# triversity.net
KiCad netlist of a schematic drawn in EAGLE
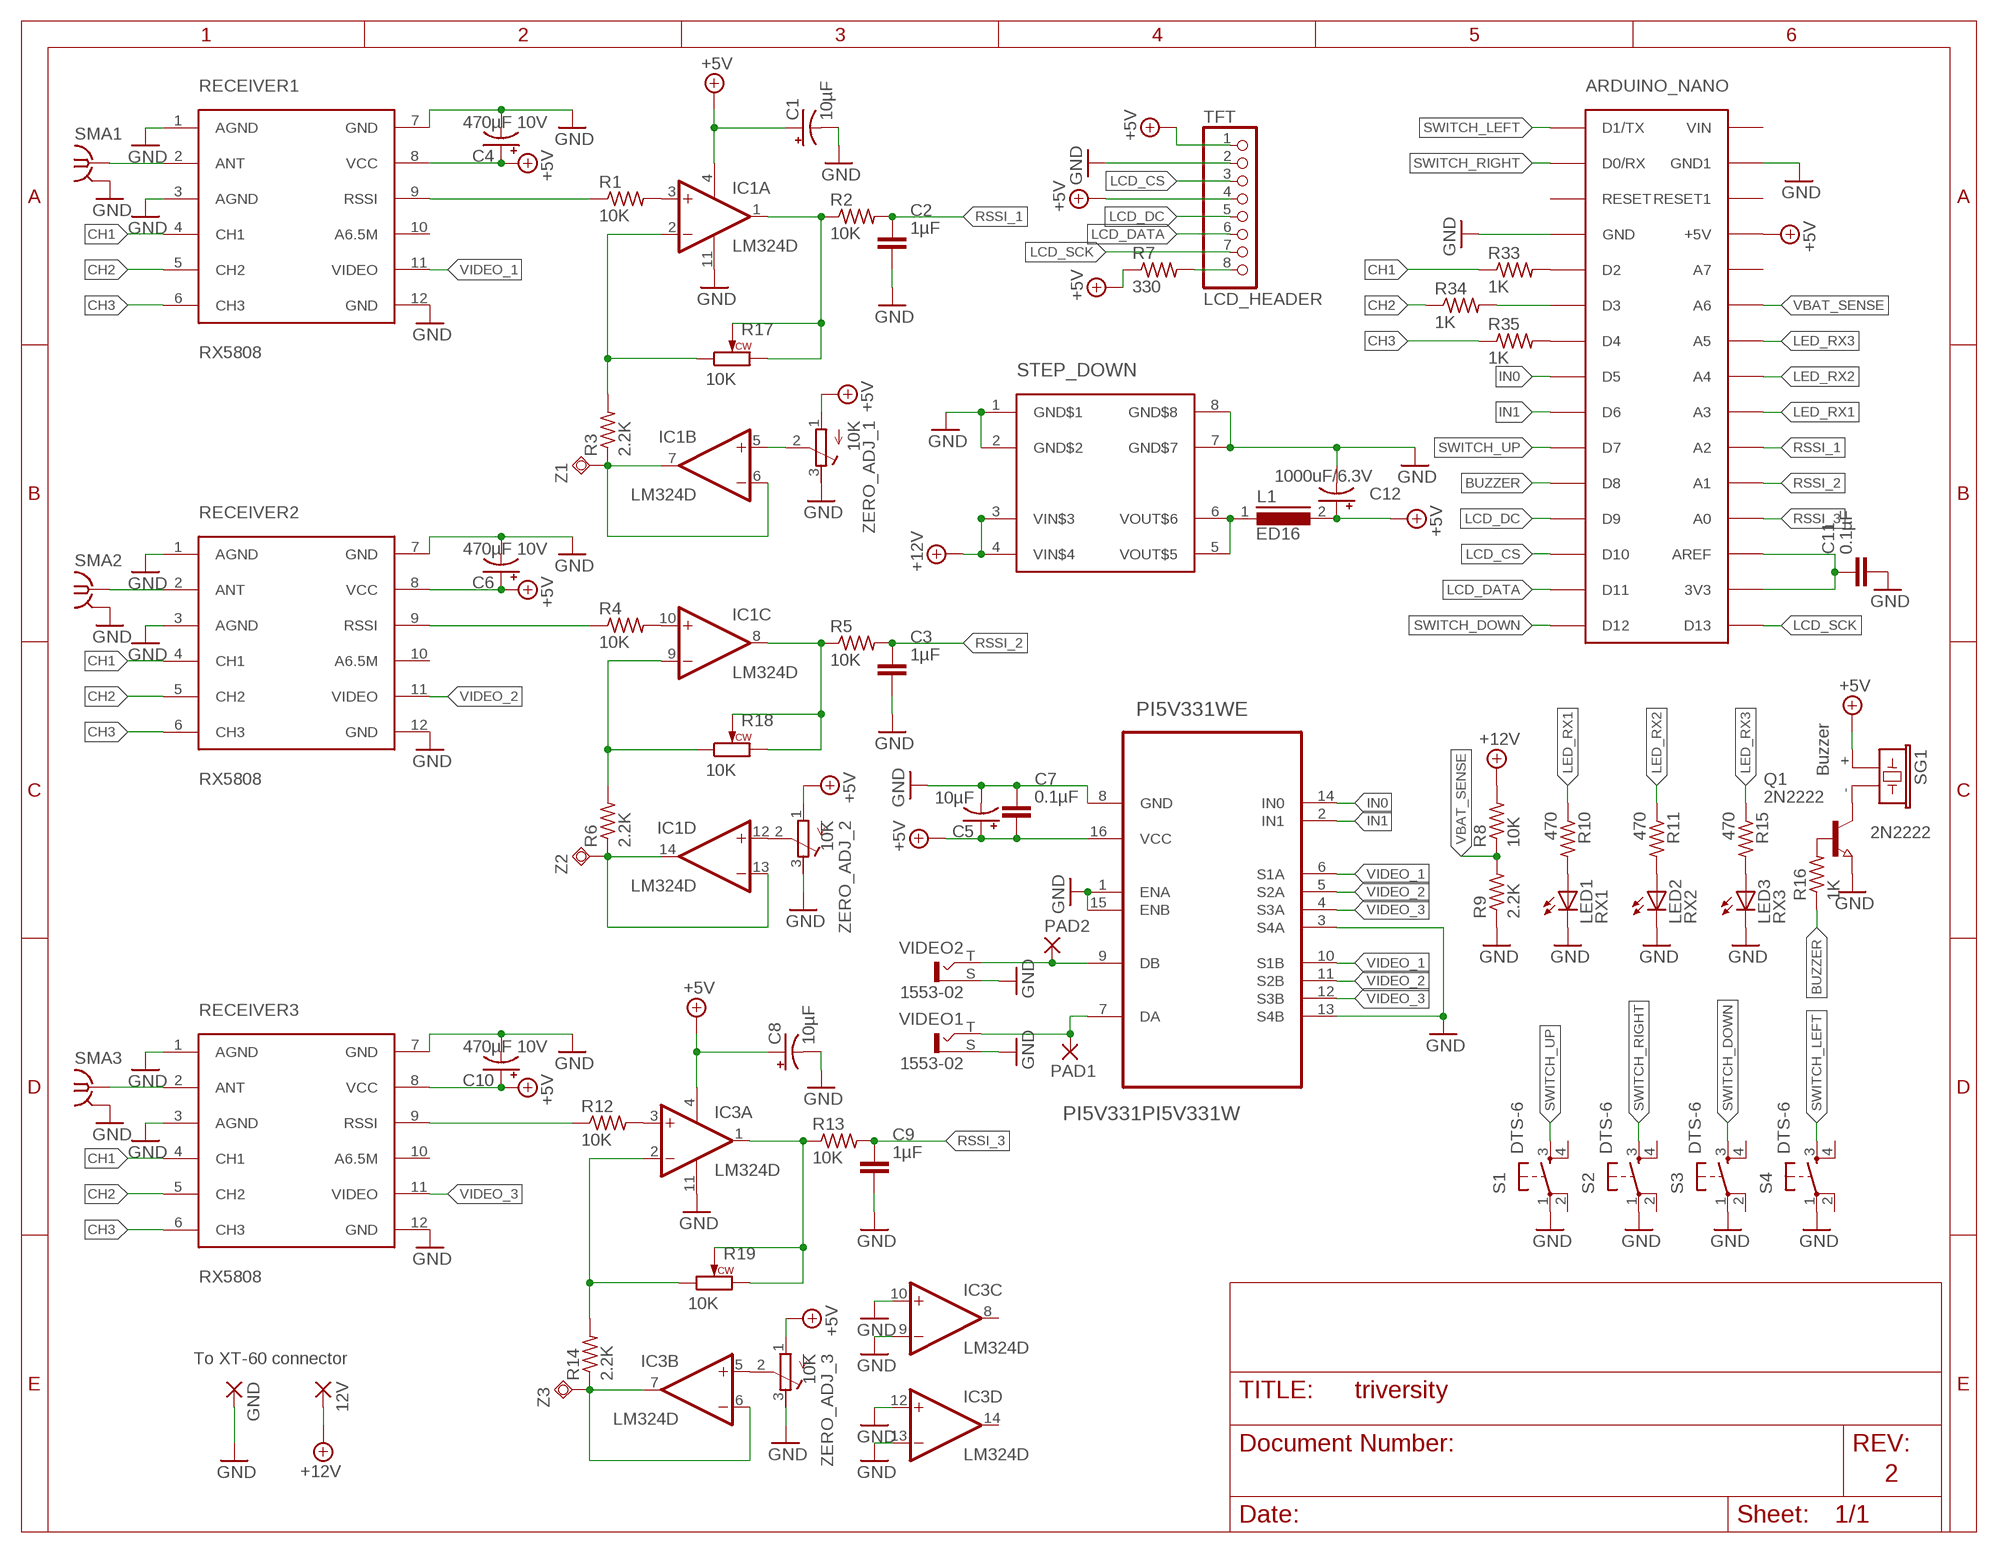
[diagram p0: schematic, sheet 1]

(export (version "E")
  (design (tool "Eeschema 10.0.6"))
  (components
    (comp (ref "12V")
      (value "WIREPAD4,16O1,6")
      (footprint "eagle-import:4,16O1,6")
      (libsource (lib "eagle-import") (part "WIREPAD4,16O1,6"))
    )
    (comp (ref "ARDUINO_NANO")
      (value "ARDUINO_NANO")
      (footprint "eagle-import:PDIP-32")
      (fields (field (name "NAME") "Arduino Nano"))
      (libsource (lib "eagle-import") (part "ARDUINO_NANO"))
    )
    (comp (ref "C1")
      (value "10µF")
      (footprint "eagle-import:EIA3216-KIT")
      (libsource (lib "eagle-import") (part "CAP_POL1206-KIT"))
    )
    (comp (ref "C2")
      (value "1µF")
      (footprint "eagle-import:C805")
      (libsource (lib "eagle-import") (part "CAPACITOR_NPOL-0805"))
    )
    (comp (ref "C3")
      (value "1µF")
      (footprint "eagle-import:C805")
      (libsource (lib "eagle-import") (part "CAPACITOR_NPOL-0805"))
    )
    (comp (ref "C4")
      (value "470µF 10V")
      (footprint "eagle-import:EIA7343")
      (libsource (lib "eagle-import") (part "CAP_POL7343"))
    )
    (comp (ref "C5")
      (value "10µF")
      (footprint "eagle-import:EIA3216-KIT")
      (libsource (lib "eagle-import") (part "CAP_POL1206-KIT"))
    )
    (comp (ref "C6")
      (value "470µF 10V")
      (footprint "eagle-import:EIA7343")
      (libsource (lib "eagle-import") (part "CAP_POL7343"))
    )
    (comp (ref "C7")
      (value "0.1µF")
      (footprint "eagle-import:C805")
      (libsource (lib "eagle-import") (part "CAPACITOR_NPOL-0805"))
    )
    (comp (ref "C8")
      (value "10µF")
      (footprint "eagle-import:EIA3216-KIT")
      (libsource (lib "eagle-import") (part "CAP_POL1206-KIT"))
    )
    (comp (ref "C9")
      (value "1µF")
      (footprint "eagle-import:C805")
      (libsource (lib "eagle-import") (part "CAPACITOR_NPOL-0805"))
    )
    (comp (ref "C10")
      (value "470µF 10V")
      (footprint "eagle-import:EIA7343")
      (libsource (lib "eagle-import") (part "CAP_POL7343"))
    )
    (comp (ref "C11")
      (value "0.1µF")
      (footprint "eagle-import:C805")
      (libsource (lib "eagle-import") (part "CAPACITOR_NPOL-0805"))
    )
    (comp (ref "C12")
      (value "1000uF/6.3V")
      (footprint "eagle-import:E5-10,5")
      (libsource (lib "eagle-import") (part "CPOL-USE5-10.5"))
    )
    (comp (ref "GND")
      (value "WIREPAD4,16O1,6")
      (footprint "eagle-import:4,16O1,6")
      (libsource (lib "eagle-import") (part "WIREPAD4,16O1,6"))
    )
    (comp (ref "IC1")
      (value "LM324D")
      (footprint "eagle-import:SO14")
      (libsource (lib "eagle-import") (part "LM324D"))
    )
    (comp (ref "IC3")
      (value "LM324D")
      (footprint "eagle-import:SO14")
      (libsource (lib "eagle-import") (part "LM324D"))
    )
    (comp (ref "L1")
      (value "ED16")
      (footprint "eagle-import:ED16")
      (libsource (lib "eagle-import") (part "ED16"))
    )
    (comp (ref "LED1")
      (value "RX1")
      (footprint "eagle-import:LED3MM")
      (libsource (lib "eagle-import") (part "LED3MM"))
    )
    (comp (ref "LED2")
      (value "RX2")
      (footprint "eagle-import:LED3MM")
      (libsource (lib "eagle-import") (part "LED3MM"))
    )
    (comp (ref "LED3")
      (value "RX3")
      (footprint "eagle-import:LED3MM")
      (libsource (lib "eagle-import") (part "LED3MM"))
    )
    (comp (ref "PAD1")
      (value "WIREPADSMD1,27-254")
      (footprint "eagle-import:SMD1,27-2,54")
      (libsource (lib "eagle-import") (part "WIREPADSMD1,27-254"))
    )
    (comp (ref "PAD2")
      (value "WIREPADSMD1,27-254")
      (footprint "eagle-import:SMD1,27-2,54")
      (libsource (lib "eagle-import") (part "WIREPADSMD1,27-254"))
    )
    (comp (ref "PI5V331WE")
      (value "PI5V331PI5V331W")
      (footprint "eagle-import:SO16")
      (libsource (lib "eagle-import") (part "PI5V331PI5V331W"))
    )
    (comp (ref "Q1")
      (value "2N2222")
      (footprint "eagle-import:SOT23")
      (libsource (lib "eagle-import") (part "NPN-TRANSISTOR_SOT23"))
    )
    (comp (ref "R1")
      (value "10K")
      (footprint "eagle-import:M0805")
      (libsource (lib "eagle-import") (part "R-US_M0805"))
    )
    (comp (ref "R2")
      (value "10K")
      (footprint "eagle-import:M0805")
      (libsource (lib "eagle-import") (part "R-US_M0805"))
    )
    (comp (ref "R3")
      (value "2.2K")
      (footprint "eagle-import:M0805")
      (libsource (lib "eagle-import") (part "R-US_M0805"))
    )
    (comp (ref "R4")
      (value "10K")
      (footprint "eagle-import:M0805")
      (libsource (lib "eagle-import") (part "R-US_M0805"))
    )
    (comp (ref "R5")
      (value "10K")
      (footprint "eagle-import:M0805")
      (libsource (lib "eagle-import") (part "R-US_M0805"))
    )
    (comp (ref "R6")
      (value "2.2K")
      (footprint "eagle-import:M0805")
      (libsource (lib "eagle-import") (part "R-US_M0805"))
    )
    (comp (ref "R7")
      (value "330")
      (footprint "eagle-import:M0805")
      (libsource (lib "eagle-import") (part "R-US_M0805"))
    )
    (comp (ref "R8")
      (value "10K")
      (footprint "eagle-import:M0805")
      (libsource (lib "eagle-import") (part "R-US_M0805"))
    )
    (comp (ref "R9")
      (value "2.2K")
      (footprint "eagle-import:M0805")
      (libsource (lib "eagle-import") (part "R-US_M0805"))
    )
    (comp (ref "R10")
      (value "470")
      (footprint "eagle-import:M0805")
      (libsource (lib "eagle-import") (part "R-US_M0805"))
    )
    (comp (ref "R11")
      (value "470")
      (footprint "eagle-import:M0805")
      (libsource (lib "eagle-import") (part "R-US_M0805"))
    )
    (comp (ref "R12")
      (value "10K")
      (footprint "eagle-import:M0805")
      (libsource (lib "eagle-import") (part "R-US_M0805"))
    )
    (comp (ref "R13")
      (value "10K")
      (footprint "eagle-import:M0805")
      (libsource (lib "eagle-import") (part "R-US_M0805"))
    )
    (comp (ref "R14")
      (value "2.2K")
      (footprint "eagle-import:M0805")
      (libsource (lib "eagle-import") (part "R-US_M0805"))
    )
    (comp (ref "R15")
      (value "470")
      (footprint "eagle-import:M0805")
      (libsource (lib "eagle-import") (part "R-US_M0805"))
    )
    (comp (ref "R16")
      (value "1K")
      (footprint "eagle-import:M0805")
      (libsource (lib "eagle-import") (part "R-US_M0805"))
    )
    (comp (ref "R17")
      (value "10K")
      (footprint "eagle-import:RK09L-SINGLE")
      (libsource (lib "eagle-import") (part "POT-SINGLE-RK09L"))
    )
    (comp (ref "R18")
      (value "10K")
      (footprint "eagle-import:RK09L-SINGLE")
      (libsource (lib "eagle-import") (part "POT-SINGLE-RK09L"))
    )
    (comp (ref "R19")
      (value "10K")
      (footprint "eagle-import:RK09L-SINGLE")
      (libsource (lib "eagle-import") (part "POT-SINGLE-RK09L"))
    )
    (comp (ref "R33")
      (value "1K")
      (footprint "eagle-import:M0805")
      (libsource (lib "eagle-import") (part "R-US_M0805"))
    )
    (comp (ref "R34")
      (value "1K")
      (footprint "eagle-import:M0805")
      (libsource (lib "eagle-import") (part "R-US_M0805"))
    )
    (comp (ref "R35")
      (value "1K")
      (footprint "eagle-import:M0805")
      (libsource (lib "eagle-import") (part "R-US_M0805"))
    )
    (comp (ref "RECEIVER1")
      (value "RX5808")
      (footprint "eagle-import:RX5808")
      (libsource (lib "eagle-import") (part "RX5808V1"))
    )
    (comp (ref "RECEIVER2")
      (value "RX5808")
      (footprint "eagle-import:RX5808")
      (libsource (lib "eagle-import") (part "RX5808V1"))
    )
    (comp (ref "RECEIVER3")
      (value "RX5808")
      (footprint "eagle-import:RX5808")
      (libsource (lib "eagle-import") (part "RX5808V1"))
    )
    (comp (ref "S1")
      (value "DTS-6")
      (footprint "eagle-import:DTS-6")
      (libsource (lib "eagle-import") (part "DTS-6"))
    )
    (comp (ref "S2")
      (value "DTS-6")
      (footprint "eagle-import:DTS-6")
      (libsource (lib "eagle-import") (part "DTS-6"))
    )
    (comp (ref "S3")
      (value "DTS-6")
      (footprint "eagle-import:DTS-6")
      (libsource (lib "eagle-import") (part "DTS-6"))
    )
    (comp (ref "S4")
      (value "DTS-6")
      (footprint "eagle-import:DTS-6")
      (libsource (lib "eagle-import") (part "DTS-6"))
    )
    (comp (ref "SG1")
      (value "Buzzer")
      (footprint "eagle-import:F_CM12P")
      (libsource (lib "eagle-import") (part "F/CM12P"))
    )
    (comp (ref "SMA1")
      (value "SMA-142-0711-821/826")
      (footprint "eagle-import:J502-ND-142-0711-821_826")
      (libsource (lib "eagle-import") (part "SMA-142-0711-821/826"))
    )
    (comp (ref "SMA2")
      (value "SMA-142-0711-821/826")
      (footprint "eagle-import:J502-ND-142-0711-821_826")
      (libsource (lib "eagle-import") (part "SMA-142-0711-821/826"))
    )
    (comp (ref "SMA3")
      (value "SMA-142-0711-821/826")
      (footprint "eagle-import:J502-ND-142-0711-821_826")
      (libsource (lib "eagle-import") (part "SMA-142-0711-821/826"))
    )
    (comp (ref "STEP_DOWN")
      (value "LM2596_MODULE")
      (footprint "eagle-import:LM2596-MODULE")
      (libsource (lib "eagle-import") (part "LM2596_MODULE"))
    )
    (comp (ref "TFT")
      (value "LCD_HEADER")
      (footprint "eagle-import:1X08-CLEANBIG")
      (libsource (lib "eagle-import") (part "PINHD-1X8CLEANBIG"))
    )
    (comp (ref "VIDEO1")
      (value "1553-02")
      (footprint "eagle-import:1553-02")
      (libsource (lib "eagle-import") (part "1553-02"))
    )
    (comp (ref "VIDEO2")
      (value "1553-02")
      (footprint "eagle-import:1553-02")
      (libsource (lib "eagle-import") (part "1553-02"))
    )
    (comp (ref "Z1")
      (value "TP-M")
      (footprint "eagle-import:KEY-MINIATURE")
      (libsource (lib "eagle-import") (part "TP-M"))
    )
    (comp (ref "Z2")
      (value "TP-M")
      (footprint "eagle-import:KEY-MINIATURE")
      (libsource (lib "eagle-import") (part "TP-M"))
    )
    (comp (ref "Z3")
      (value "TP-M")
      (footprint "eagle-import:KEY-MINIATURE")
      (libsource (lib "eagle-import") (part "TP-M"))
    )
    (comp (ref "ZERO_ADJ_1")
      (value "10K")
      (footprint "eagle-import:RTRIM3296X")
      (libsource (lib "eagle-import") (part "R-TRIMM3296X"))
    )
    (comp (ref "ZERO_ADJ_2")
      (value "10K")
      (footprint "eagle-import:RTRIM3296X")
      (libsource (lib "eagle-import") (part "R-TRIMM3296X"))
    )
    (comp (ref "ZERO_ADJ_3")
      (value "10K")
      (footprint "eagle-import:RTRIM3296X")
      (libsource (lib "eagle-import") (part "R-TRIMM3296X"))
    )
  )
  (nets
    (net (code "1") (name "+5V") (class "Default")
      (node (ref "ARDUINO_NANO") (pin "+5V") (pinfunction "+5V_+5V") (pintype "bidirectional"))
      (node (ref "C1") (pin "A") (pinfunction "+_A") (pintype "passive"))
      (node (ref "C10") (pin "A") (pinfunction "+_A") (pintype "passive"))
      (node (ref "C12") (pin "+") (pinfunction "+_+") (pintype "passive"))
      (node (ref "C4") (pin "A") (pinfunction "+_A") (pintype "passive"))
      (node (ref "C5") (pin "A") (pinfunction "+_A") (pintype "passive"))
      (node (ref "C6") (pin "A") (pinfunction "+_A") (pintype "passive"))
      (node (ref "C7") (pin "2") (pinfunction "2_2") (pintype "passive"))
      (node (ref "C8") (pin "A") (pinfunction "+_A") (pintype "passive"))
      (node (ref "IC1") (pin "4") (pinfunction "V+_4") (pintype "power_in"))
      (node (ref "IC3") (pin "4") (pinfunction "V+_4") (pintype "power_in"))
      (node (ref "L1") (pin "2") (pinfunction "2_2") (pintype "passive"))
      (node (ref "PI5V331WE") (pin "16") (pinfunction "VCC_16") (pintype "power_in"))
      (node (ref "R7") (pin "1") (pinfunction "1_1") (pintype "passive"))
      (node (ref "RECEIVER1") (pin "8") (pinfunction "VCC_8") (pintype "power_in"))
      (node (ref "RECEIVER2") (pin "8") (pinfunction "VCC_8") (pintype "power_in"))
      (node (ref "RECEIVER3") (pin "8") (pinfunction "VCC_8") (pintype "power_in"))
      (node (ref "SG1") (pin "+") (pinfunction "1_+") (pintype "passive"))
      (node (ref "TFT") (pin "1") (pinfunction "1_1") (pintype "passive"))
      (node (ref "TFT") (pin "4") (pinfunction "4_4") (pintype "passive"))
      (node (ref "ZERO_ADJ_1") (pin "1") (pinfunction "E_1") (pintype "passive"))
      (node (ref "ZERO_ADJ_2") (pin "1") (pinfunction "E_1") (pintype "passive"))
      (node (ref "ZERO_ADJ_3") (pin "1") (pinfunction "E_1") (pintype "passive"))
    )
    (net (code "2") (name "+12V") (class "Default")
      (node (ref "12V") (pin "1") (pinfunction "P_1") (pintype "passive"))
      (node (ref "R8") (pin "2") (pinfunction "2_2") (pintype "passive"))
      (node (ref "STEP_DOWN") (pin "3") (pinfunction "VIN$3_3") (pintype "power_in"))
      (node (ref "STEP_DOWN") (pin "4") (pinfunction "VIN$4_4") (pintype "power_in"))
    )
    (net (code "3") (name "BUZZER") (class "Default")
      (node (ref "ARDUINO_NANO") (pin "D8") (pinfunction "D8_D8") (pintype "bidirectional"))
      (node (ref "R16") (pin "1") (pinfunction "1_1") (pintype "passive"))
    )
    (net (code "4") (name "CH1") (class "Default")
      (node (ref "R33") (pin "1") (pinfunction "1_1") (pintype "passive"))
      (node (ref "RECEIVER1") (pin "4") (pinfunction "CH1_4") (pintype "input"))
      (node (ref "RECEIVER2") (pin "4") (pinfunction "CH1_4") (pintype "input"))
      (node (ref "RECEIVER3") (pin "4") (pinfunction "CH1_4") (pintype "input"))
    )
    (net (code "5") (name "CH2") (class "Default")
      (node (ref "R34") (pin "1") (pinfunction "1_1") (pintype "passive"))
      (node (ref "RECEIVER1") (pin "5") (pinfunction "CH2_5") (pintype "input"))
      (node (ref "RECEIVER2") (pin "5") (pinfunction "CH2_5") (pintype "input"))
      (node (ref "RECEIVER3") (pin "5") (pinfunction "CH2_5") (pintype "input"))
    )
    (net (code "6") (name "CH3") (class "Default")
      (node (ref "R35") (pin "1") (pinfunction "1_1") (pintype "passive"))
      (node (ref "RECEIVER1") (pin "6") (pinfunction "CH3_6") (pintype "input"))
      (node (ref "RECEIVER2") (pin "6") (pinfunction "CH3_6") (pintype "input"))
      (node (ref "RECEIVER3") (pin "6") (pinfunction "CH3_6") (pintype "input"))
    )
    (net (code "7") (name "GND") (class "Default")
      (node (ref "ARDUINO_NANO") (pin "GND") (pinfunction "GND_GND") (pintype "bidirectional"))
      (node (ref "ARDUINO_NANO") (pin "GND1") (pinfunction "GND1_GND1") (pintype "bidirectional"))
      (node (ref "C1") (pin "C") (pinfunction "-_C") (pintype "passive"))
      (node (ref "C10") (pin "C") (pinfunction "-_C") (pintype "passive"))
      (node (ref "C11") (pin "2") (pinfunction "2_2") (pintype "passive"))
      (node (ref "C12") (pin "-") (pinfunction "-_-") (pintype "passive"))
      (node (ref "C2") (pin "2") (pinfunction "2_2") (pintype "passive"))
      (node (ref "C3") (pin "2") (pinfunction "2_2") (pintype "passive"))
      (node (ref "C4") (pin "C") (pinfunction "-_C") (pintype "passive"))
      (node (ref "C5") (pin "C") (pinfunction "-_C") (pintype "passive"))
      (node (ref "C6") (pin "C") (pinfunction "-_C") (pintype "passive"))
      (node (ref "C7") (pin "1") (pinfunction "1_1") (pintype "passive"))
      (node (ref "C8") (pin "C") (pinfunction "-_C") (pintype "passive"))
      (node (ref "C9") (pin "2") (pinfunction "2_2") (pintype "passive"))
      (node (ref "GND") (pin "1") (pinfunction "P_1") (pintype "passive"))
      (node (ref "IC1") (pin "11") (pinfunction "V-_11") (pintype "power_in"))
      (node (ref "IC3") (pin "10") (pinfunction "+IN_10") (pintype "input"))
      (node (ref "IC3") (pin "11") (pinfunction "V-_11") (pintype "power_in"))
      (node (ref "IC3") (pin "12") (pinfunction "+IN_12") (pintype "input"))
      (node (ref "IC3") (pin "13") (pinfunction "-IN_13") (pintype "input"))
      (node (ref "IC3") (pin "9") (pinfunction "-IN_9") (pintype "input"))
      (node (ref "LED1") (pin "K") (pinfunction "C_K") (pintype "passive"))
      (node (ref "LED2") (pin "K") (pinfunction "C_K") (pintype "passive"))
      (node (ref "LED3") (pin "K") (pinfunction "C_K") (pintype "passive"))
      (node (ref "PI5V331WE") (pin "1") (pinfunction "ENA_1") (pintype "input"))
      (node (ref "PI5V331WE") (pin "13") (pinfunction "S4B_13") (pintype "input"))
      (node (ref "PI5V331WE") (pin "15") (pinfunction "ENB_15") (pintype "input"))
      (node (ref "PI5V331WE") (pin "3") (pinfunction "S4A_3") (pintype "input"))
      (node (ref "PI5V331WE") (pin "8") (pinfunction "GND_8") (pintype "power_in"))
      (node (ref "Q1") (pin "2") (pinfunction "E_2") (pintype "passive"))
      (node (ref "R9") (pin "1") (pinfunction "1_1") (pintype "passive"))
      (node (ref "RECEIVER1") (pin "1") (pinfunction "AGND_1") (pintype "input"))
      (node (ref "RECEIVER1") (pin "12") (pinfunction "GND_12") (pintype "power_in"))
      (node (ref "RECEIVER1") (pin "3") (pinfunction "AGND_3") (pintype "input"))
      (node (ref "RECEIVER1") (pin "7") (pinfunction "GND_7") (pintype "power_in"))
      (node (ref "RECEIVER2") (pin "1") (pinfunction "AGND_1") (pintype "input"))
      (node (ref "RECEIVER2") (pin "12") (pinfunction "GND_12") (pintype "power_in"))
      (node (ref "RECEIVER2") (pin "3") (pinfunction "AGND_3") (pintype "input"))
      (node (ref "RECEIVER2") (pin "7") (pinfunction "GND_7") (pintype "power_in"))
      (node (ref "RECEIVER3") (pin "1") (pinfunction "AGND_1") (pintype "input"))
      (node (ref "RECEIVER3") (pin "12") (pinfunction "GND_12") (pintype "power_in"))
      (node (ref "RECEIVER3") (pin "3") (pinfunction "AGND_3") (pintype "input"))
      (node (ref "RECEIVER3") (pin "7") (pinfunction "GND_7") (pintype "power_in"))
      (node (ref "S1") (pin "1") (pinfunction "1_1") (pintype "passive"))
      (node (ref "S2") (pin "1") (pinfunction "1_1") (pintype "passive"))
      (node (ref "S3") (pin "1") (pinfunction "1_1") (pintype "passive"))
      (node (ref "S4") (pin "1") (pinfunction "1_1") (pintype "passive"))
      (node (ref "SMA1") (pin "G@1") (pinfunction "GND_G@1") (pintype "power_in"))
      (node (ref "SMA2") (pin "G@1") (pinfunction "GND_G@1") (pintype "power_in"))
      (node (ref "SMA3") (pin "G@1") (pinfunction "GND_G@1") (pintype "power_in"))
      (node (ref "STEP_DOWN") (pin "1") (pinfunction "GND$1_1") (pintype "power_in"))
      (node (ref "STEP_DOWN") (pin "2") (pinfunction "GND$2_2") (pintype "power_in"))
      (node (ref "STEP_DOWN") (pin "7") (pinfunction "GND$7_7") (pintype "power_in"))
      (node (ref "STEP_DOWN") (pin "8") (pinfunction "GND$8_8") (pintype "power_in"))
      (node (ref "TFT") (pin "2") (pinfunction "2_2") (pintype "passive"))
      (node (ref "VIDEO1") (pin "S") (pinfunction "S_S") (pintype "passive"))
      (node (ref "VIDEO2") (pin "S") (pinfunction "S_S") (pintype "passive"))
      (node (ref "ZERO_ADJ_1") (pin "3") (pinfunction "A_3") (pintype "passive"))
      (node (ref "ZERO_ADJ_2") (pin "3") (pinfunction "A_3") (pintype "passive"))
      (node (ref "ZERO_ADJ_3") (pin "3") (pinfunction "A_3") (pintype "passive"))
    )
    (net (code "8") (name "IN0") (class "Default")
      (node (ref "ARDUINO_NANO") (pin "D5") (pinfunction "D5_D5") (pintype "bidirectional"))
      (node (ref "PI5V331WE") (pin "14") (pinfunction "IN0_14") (pintype "input"))
    )
    (net (code "9") (name "IN1") (class "Default")
      (node (ref "ARDUINO_NANO") (pin "D6") (pinfunction "D6_D6") (pintype "bidirectional"))
      (node (ref "PI5V331WE") (pin "2") (pinfunction "IN1_2") (pintype "input"))
    )
    (net (code "10") (name "LCD_CS") (class "Default")
      (node (ref "ARDUINO_NANO") (pin "D10") (pinfunction "D10_D10") (pintype "bidirectional"))
      (node (ref "TFT") (pin "3") (pinfunction "3_3") (pintype "passive"))
    )
    (net (code "11") (name "LCD_DATA") (class "Default")
      (node (ref "ARDUINO_NANO") (pin "D11") (pinfunction "D11_D11") (pintype "bidirectional"))
      (node (ref "TFT") (pin "6") (pinfunction "6_6") (pintype "passive"))
    )
    (net (code "12") (name "LCD_DC") (class "Default")
      (node (ref "ARDUINO_NANO") (pin "D9") (pinfunction "D9_D9") (pintype "bidirectional"))
      (node (ref "TFT") (pin "5") (pinfunction "5_5") (pintype "passive"))
    )
    (net (code "13") (name "LCD_SCK") (class "Default")
      (node (ref "ARDUINO_NANO") (pin "D13") (pinfunction "D13_D13") (pintype "bidirectional"))
      (node (ref "TFT") (pin "7") (pinfunction "7_7") (pintype "passive"))
    )
    (net (code "14") (name "LED_RX1") (class "Default")
      (node (ref "ARDUINO_NANO") (pin "A3") (pinfunction "A3_A3") (pintype "bidirectional"))
      (node (ref "R10") (pin "1") (pinfunction "1_1") (pintype "passive"))
    )
    (net (code "15") (name "LED_RX2") (class "Default")
      (node (ref "ARDUINO_NANO") (pin "A4") (pinfunction "A4_A4") (pintype "bidirectional"))
      (node (ref "R11") (pin "1") (pinfunction "1_1") (pintype "passive"))
    )
    (net (code "16") (name "LED_RX3") (class "Default")
      (node (ref "ARDUINO_NANO") (pin "A5") (pinfunction "A5_A5") (pintype "bidirectional"))
      (node (ref "R15") (pin "1") (pinfunction "1_1") (pintype "passive"))
    )
    (net (code "17") (name "Net-(ARDUINO_NANO-Pad3V3)") (class "Default")
      (node (ref "ARDUINO_NANO") (pin "3V3") (pinfunction "3V3_3V3") (pintype "bidirectional"))
      (node (ref "ARDUINO_NANO") (pin "AREF") (pinfunction "AREF_AREF") (pintype "bidirectional"))
      (node (ref "C11") (pin "1") (pinfunction "1_1") (pintype "passive"))
    )
    (net (code "18") (name "Net-(ARDUINO_NANO-PadD2)") (class "Default")
      (node (ref "ARDUINO_NANO") (pin "D2") (pinfunction "D2_D2") (pintype "bidirectional"))
      (node (ref "R33") (pin "2") (pinfunction "2_2") (pintype "passive"))
    )
    (net (code "19") (name "Net-(ARDUINO_NANO-PadD3)") (class "Default")
      (node (ref "ARDUINO_NANO") (pin "D3") (pinfunction "D3_D3") (pintype "bidirectional"))
      (node (ref "R34") (pin "2") (pinfunction "2_2") (pintype "passive"))
    )
    (net (code "20") (name "Net-(ARDUINO_NANO-PadD4)") (class "Default")
      (node (ref "ARDUINO_NANO") (pin "D4") (pinfunction "D4_D4") (pintype "bidirectional"))
      (node (ref "R35") (pin "2") (pinfunction "2_2") (pintype "passive"))
    )
    (net (code "21") (name "Net-(IC1A-+IN)") (class "Default")
      (node (ref "IC1") (pin "3") (pinfunction "+IN_3") (pintype "input"))
      (node (ref "R1") (pin "2") (pinfunction "2_2") (pintype "passive"))
    )
    (net (code "22") (name "Net-(IC1A--IN)") (class "Default")
      (node (ref "IC1") (pin "2") (pinfunction "-IN_2") (pintype "input"))
      (node (ref "R17") (pin "1") (pinfunction "CCW_1") (pintype "passive"))
      (node (ref "R3") (pin "2") (pinfunction "2_2") (pintype "passive"))
    )
    (net (code "23") (name "Net-(IC1A-OUT)") (class "Default")
      (node (ref "IC1") (pin "1") (pinfunction "OUT_1") (pintype "output"))
      (node (ref "R17") (pin "2") (pinfunction "W_2") (pintype "passive"))
      (node (ref "R17") (pin "3") (pinfunction "CW_3") (pintype "passive"))
      (node (ref "R2") (pin "1") (pinfunction "1_1") (pintype "passive"))
    )
    (net (code "24") (name "Net-(IC1B-+IN)") (class "Default")
      (node (ref "IC1") (pin "5") (pinfunction "+IN_5") (pintype "input"))
      (node (ref "ZERO_ADJ_1") (pin "2") (pinfunction "S_2") (pintype "passive"))
    )
    (net (code "25") (name "Net-(IC1B--IN)") (class "Default")
      (node (ref "IC1") (pin "6") (pinfunction "-IN_6") (pintype "input"))
      (node (ref "IC1") (pin "7") (pinfunction "OUT_7") (pintype "output"))
      (node (ref "R3") (pin "1") (pinfunction "1_1") (pintype "passive"))
      (node (ref "Z1") (pin "P$1") (pinfunction "TP_P$1") (pintype "input"))
    )
    (net (code "26") (name "Net-(IC1C-+IN)") (class "Default")
      (node (ref "IC1") (pin "10") (pinfunction "+IN_10") (pintype "input"))
      (node (ref "R4") (pin "2") (pinfunction "2_2") (pintype "passive"))
    )
    (net (code "27") (name "Net-(IC1C--IN)") (class "Default")
      (node (ref "IC1") (pin "9") (pinfunction "-IN_9") (pintype "input"))
      (node (ref "R18") (pin "1") (pinfunction "CCW_1") (pintype "passive"))
      (node (ref "R6") (pin "2") (pinfunction "2_2") (pintype "passive"))
    )
    (net (code "28") (name "Net-(IC1C-OUT)") (class "Default")
      (node (ref "IC1") (pin "8") (pinfunction "OUT_8") (pintype "output"))
      (node (ref "R18") (pin "2") (pinfunction "W_2") (pintype "passive"))
      (node (ref "R18") (pin "3") (pinfunction "CW_3") (pintype "passive"))
      (node (ref "R5") (pin "1") (pinfunction "1_1") (pintype "passive"))
    )
    (net (code "29") (name "Net-(IC1D-+IN)") (class "Default")
      (node (ref "IC1") (pin "12") (pinfunction "+IN_12") (pintype "input"))
      (node (ref "ZERO_ADJ_2") (pin "2") (pinfunction "S_2") (pintype "passive"))
    )
    (net (code "30") (name "Net-(IC1D--IN)") (class "Default")
      (node (ref "IC1") (pin "13") (pinfunction "-IN_13") (pintype "input"))
      (node (ref "IC1") (pin "14") (pinfunction "OUT_14") (pintype "output"))
      (node (ref "R6") (pin "1") (pinfunction "1_1") (pintype "passive"))
      (node (ref "Z2") (pin "P$1") (pinfunction "TP_P$1") (pintype "input"))
    )
    (net (code "31") (name "Net-(IC3A-+IN)") (class "Default")
      (node (ref "IC3") (pin "3") (pinfunction "+IN_3") (pintype "input"))
      (node (ref "R12") (pin "2") (pinfunction "2_2") (pintype "passive"))
    )
    (net (code "32") (name "Net-(IC3A--IN)") (class "Default")
      (node (ref "IC3") (pin "2") (pinfunction "-IN_2") (pintype "input"))
      (node (ref "R14") (pin "2") (pinfunction "2_2") (pintype "passive"))
      (node (ref "R19") (pin "1") (pinfunction "CCW_1") (pintype "passive"))
    )
    (net (code "33") (name "Net-(IC3A-OUT)") (class "Default")
      (node (ref "IC3") (pin "1") (pinfunction "OUT_1") (pintype "output"))
      (node (ref "R13") (pin "1") (pinfunction "1_1") (pintype "passive"))
      (node (ref "R19") (pin "2") (pinfunction "W_2") (pintype "passive"))
      (node (ref "R19") (pin "3") (pinfunction "CW_3") (pintype "passive"))
    )
    (net (code "34") (name "Net-(IC3B-+IN)") (class "Default")
      (node (ref "IC3") (pin "5") (pinfunction "+IN_5") (pintype "input"))
      (node (ref "ZERO_ADJ_3") (pin "2") (pinfunction "S_2") (pintype "passive"))
    )
    (net (code "35") (name "Net-(IC3B--IN)") (class "Default")
      (node (ref "IC3") (pin "6") (pinfunction "-IN_6") (pintype "input"))
      (node (ref "IC3") (pin "7") (pinfunction "OUT_7") (pintype "output"))
      (node (ref "R14") (pin "1") (pinfunction "1_1") (pintype "passive"))
      (node (ref "Z3") (pin "P$1") (pinfunction "TP_P$1") (pintype "input"))
    )
    (net (code "36") (name "Net-(LED1-PadA)") (class "Default")
      (node (ref "LED1") (pin "A") (pinfunction "A_A") (pintype "passive"))
      (node (ref "R10") (pin "2") (pinfunction "2_2") (pintype "passive"))
    )
    (net (code "37") (name "Net-(LED2-PadA)") (class "Default")
      (node (ref "LED2") (pin "A") (pinfunction "A_A") (pintype "passive"))
      (node (ref "R11") (pin "2") (pinfunction "2_2") (pintype "passive"))
    )
    (net (code "38") (name "Net-(LED3-PadA)") (class "Default")
      (node (ref "LED3") (pin "A") (pinfunction "A_A") (pintype "passive"))
      (node (ref "R15") (pin "2") (pinfunction "2_2") (pintype "passive"))
    )
    (net (code "39") (name "Net-(PAD1-P)") (class "Default")
      (node (ref "PAD1") (pin "1") (pinfunction "P_1") (pintype "passive"))
      (node (ref "PI5V331WE") (pin "7") (pinfunction "DA_7") (pintype "output"))
      (node (ref "VIDEO1") (pin "T") (pinfunction "T_T") (pintype "passive"))
    )
    (net (code "40") (name "Net-(PAD2-P)") (class "Default")
      (node (ref "PAD2") (pin "1") (pinfunction "P_1") (pintype "passive"))
      (node (ref "PI5V331WE") (pin "9") (pinfunction "DB_9") (pintype "output"))
      (node (ref "VIDEO2") (pin "T") (pinfunction "T_T") (pintype "passive"))
    )
    (net (code "41") (name "Net-(Q1-B)") (class "Default")
      (node (ref "Q1") (pin "1") (pinfunction "B_1") (pintype "passive"))
      (node (ref "R16") (pin "2") (pinfunction "2_2") (pintype "passive"))
    )
    (net (code "42") (name "Net-(Q1-C)") (class "Default")
      (node (ref "Q1") (pin "3") (pinfunction "C_3") (pintype "passive"))
      (node (ref "SG1") (pin "-") (pinfunction "2_-") (pintype "passive"))
    )
    (net (code "43") (name "Net-(R7-Pad2)") (class "Default")
      (node (ref "R7") (pin "2") (pinfunction "2_2") (pintype "passive"))
      (node (ref "TFT") (pin "8") (pinfunction "8_8") (pintype "passive"))
    )
    (net (code "44") (name "Net-(RECEIVER1-ANT)") (class "Default")
      (node (ref "RECEIVER1") (pin "2") (pinfunction "ANT_2") (pintype "input"))
      (node (ref "SMA1") (pin "1") (pinfunction "1_1") (pintype "passive"))
    )
    (net (code "45") (name "Net-(RECEIVER1-RSSI)") (class "Default")
      (node (ref "R1") (pin "1") (pinfunction "1_1") (pintype "passive"))
      (node (ref "RECEIVER1") (pin "9") (pinfunction "RSSI_9") (pintype "output"))
    )
    (net (code "46") (name "Net-(RECEIVER2-ANT)") (class "Default")
      (node (ref "RECEIVER2") (pin "2") (pinfunction "ANT_2") (pintype "input"))
      (node (ref "SMA2") (pin "1") (pinfunction "1_1") (pintype "passive"))
    )
    (net (code "47") (name "Net-(RECEIVER2-RSSI)") (class "Default")
      (node (ref "R4") (pin "1") (pinfunction "1_1") (pintype "passive"))
      (node (ref "RECEIVER2") (pin "9") (pinfunction "RSSI_9") (pintype "output"))
    )
    (net (code "48") (name "Net-(RECEIVER3-ANT)") (class "Default")
      (node (ref "RECEIVER3") (pin "2") (pinfunction "ANT_2") (pintype "input"))
      (node (ref "SMA3") (pin "1") (pinfunction "1_1") (pintype "passive"))
    )
    (net (code "49") (name "Net-(RECEIVER3-RSSI)") (class "Default")
      (node (ref "R12") (pin "1") (pinfunction "1_1") (pintype "passive"))
      (node (ref "RECEIVER3") (pin "9") (pinfunction "RSSI_9") (pintype "output"))
    )
    (net (code "50") (name "Net-(STEP_DOWN-VOUT$5)") (class "Default")
      (node (ref "L1") (pin "1") (pinfunction "1_1") (pintype "passive"))
      (node (ref "STEP_DOWN") (pin "5") (pinfunction "VOUT$5_5") (pintype "power_in"))
      (node (ref "STEP_DOWN") (pin "6") (pinfunction "VOUT$6_6") (pintype "power_in"))
    )
    (net (code "51") (name "RSSI_1") (class "Default")
      (node (ref "ARDUINO_NANO") (pin "A2") (pinfunction "A2_A2") (pintype "bidirectional"))
      (node (ref "C2") (pin "1") (pinfunction "1_1") (pintype "passive"))
      (node (ref "R2") (pin "2") (pinfunction "2_2") (pintype "passive"))
    )
    (net (code "52") (name "RSSI_2") (class "Default")
      (node (ref "ARDUINO_NANO") (pin "A1") (pinfunction "A1_A1") (pintype "bidirectional"))
      (node (ref "C3") (pin "1") (pinfunction "1_1") (pintype "passive"))
      (node (ref "R5") (pin "2") (pinfunction "2_2") (pintype "passive"))
    )
    (net (code "53") (name "RSSI_3") (class "Default")
      (node (ref "ARDUINO_NANO") (pin "A0") (pinfunction "A0_A0") (pintype "bidirectional"))
      (node (ref "C9") (pin "1") (pinfunction "1_1") (pintype "passive"))
      (node (ref "R13") (pin "2") (pinfunction "2_2") (pintype "passive"))
    )
    (net (code "54") (name "SWITCH_DOWN") (class "Default")
      (node (ref "ARDUINO_NANO") (pin "D12") (pinfunction "D12_D12") (pintype "bidirectional"))
      (node (ref "S3") (pin "3") (pinfunction "3_3") (pintype "passive"))
    )
    (net (code "55") (name "SWITCH_LEFT") (class "Default")
      (node (ref "ARDUINO_NANO") (pin "D1/TX") (pinfunction "D1/TX_D1/TX") (pintype "bidirectional"))
      (node (ref "S4") (pin "3") (pinfunction "3_3") (pintype "passive"))
    )
    (net (code "56") (name "SWITCH_RIGHT") (class "Default")
      (node (ref "ARDUINO_NANO") (pin "D0/RX") (pinfunction "D0/RX_D0/RX") (pintype "bidirectional"))
      (node (ref "S2") (pin "3") (pinfunction "3_3") (pintype "passive"))
    )
    (net (code "57") (name "SWITCH_UP") (class "Default")
      (node (ref "ARDUINO_NANO") (pin "D7") (pinfunction "D7_D7") (pintype "bidirectional"))
      (node (ref "S1") (pin "3") (pinfunction "3_3") (pintype "passive"))
    )
    (net (code "58") (name "VBAT_SENSE") (class "Default")
      (node (ref "ARDUINO_NANO") (pin "A6") (pinfunction "A6_A6") (pintype "bidirectional"))
      (node (ref "R8") (pin "1") (pinfunction "1_1") (pintype "passive"))
      (node (ref "R9") (pin "2") (pinfunction "2_2") (pintype "passive"))
    )
    (net (code "59") (name "VIDEO_1") (class "Default")
      (node (ref "PI5V331WE") (pin "10") (pinfunction "S1B_10") (pintype "input"))
      (node (ref "PI5V331WE") (pin "6") (pinfunction "S1A_6") (pintype "input"))
      (node (ref "RECEIVER1") (pin "11") (pinfunction "VIDEO_11") (pintype "output"))
    )
    (net (code "60") (name "VIDEO_2") (class "Default")
      (node (ref "PI5V331WE") (pin "11") (pinfunction "S2B_11") (pintype "input"))
      (node (ref "PI5V331WE") (pin "5") (pinfunction "S2A_5") (pintype "input"))
      (node (ref "RECEIVER2") (pin "11") (pinfunction "VIDEO_11") (pintype "output"))
    )
    (net (code "61") (name "VIDEO_3") (class "Default")
      (node (ref "PI5V331WE") (pin "12") (pinfunction "S3B_12") (pintype "input"))
      (node (ref "PI5V331WE") (pin "4") (pinfunction "S3A_4") (pintype "input"))
      (node (ref "RECEIVER3") (pin "11") (pinfunction "VIDEO_11") (pintype "output"))
    )
    (net (code "62") (name "unconnected-(ARDUINO_NANO-PadA7)") (class "Default")
      (node (ref "ARDUINO_NANO") (pin "A7") (pinfunction "A7_A7") (pintype "bidirectional"))
    )
    (net (code "63") (name "unconnected-(ARDUINO_NANO-PadRESET)") (class "Default")
      (node (ref "ARDUINO_NANO") (pin "RESET") (pinfunction "RESET_RESET") (pintype "bidirectional"))
    )
    (net (code "64") (name "unconnected-(ARDUINO_NANO-PadRESET1)") (class "Default")
      (node (ref "ARDUINO_NANO") (pin "RESET1") (pinfunction "RESET1_RESET1") (pintype "bidirectional"))
    )
    (net (code "65") (name "unconnected-(ARDUINO_NANO-PadVIN)") (class "Default")
      (node (ref "ARDUINO_NANO") (pin "VIN") (pinfunction "VIN_VIN") (pintype "bidirectional"))
    )
    (net (code "66") (name "unconnected-(IC3C-OUT-Pad8)") (class "Default")
      (node (ref "IC3") (pin "8") (pinfunction "OUT_8") (pintype "output"))
    )
    (net (code "67") (name "unconnected-(IC3D-OUT-Pad14)") (class "Default")
      (node (ref "IC3") (pin "14") (pinfunction "OUT_14") (pintype "output"))
    )
    (net (code "68") (name "unconnected-(RECEIVER1-A6.5M-Pad10)") (class "Default")
      (node (ref "RECEIVER1") (pin "10") (pinfunction "A6.5M_10") (pintype "output"))
    )
    (net (code "69") (name "unconnected-(RECEIVER2-A6.5M-Pad10)") (class "Default")
      (node (ref "RECEIVER2") (pin "10") (pinfunction "A6.5M_10") (pintype "output"))
    )
    (net (code "70") (name "unconnected-(RECEIVER3-A6.5M-Pad10)") (class "Default")
      (node (ref "RECEIVER3") (pin "10") (pinfunction "A6.5M_10") (pintype "output"))
    )
    (net (code "71") (name "unconnected-(S1-Pad2)") (class "Default")
      (node (ref "S1") (pin "2") (pinfunction "2_2") (pintype "passive"))
    )
    (net (code "72") (name "unconnected-(S1-Pad4)") (class "Default")
      (node (ref "S1") (pin "4") (pinfunction "4_4") (pintype "passive"))
    )
    (net (code "73") (name "unconnected-(S2-Pad2)") (class "Default")
      (node (ref "S2") (pin "2") (pinfunction "2_2") (pintype "passive"))
    )
    (net (code "74") (name "unconnected-(S2-Pad4)") (class "Default")
      (node (ref "S2") (pin "4") (pinfunction "4_4") (pintype "passive"))
    )
    (net (code "75") (name "unconnected-(S3-Pad2)") (class "Default")
      (node (ref "S3") (pin "2") (pinfunction "2_2") (pintype "passive"))
    )
    (net (code "76") (name "unconnected-(S3-Pad4)") (class "Default")
      (node (ref "S3") (pin "4") (pinfunction "4_4") (pintype "passive"))
    )
    (net (code "77") (name "unconnected-(S4-Pad2)") (class "Default")
      (node (ref "S4") (pin "2") (pinfunction "2_2") (pintype "passive"))
    )
    (net (code "78") (name "unconnected-(S4-Pad4)") (class "Default")
      (node (ref "S4") (pin "4") (pinfunction "4_4") (pintype "passive"))
    )
  )
)
